# Load_Switch.net
KiCad netlist of a schematic drawn in Altium Designer
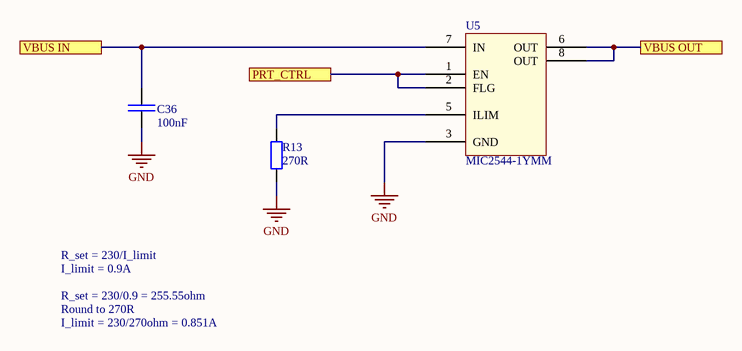
[diagram p0: Load Switch.SchDoc]

(export (version "E")
  (design (tool "Eeschema 10.0.6"))
  (components
    (comp (ref "C36")
      (value "100nF")
      (footprint "CAP_SM0603_YAGEOCC2_N")
      (description "CAP 100nF SM0603 X7R 50V YAGEO CC2")
      (fields
        (field (name "MANUFACTURER") "Yageo")
        (field (name "MANUFACTURER PART NUMBER") "CC0603KRX7R9BB104")
      )
      (libsource (lib "Yageo") (part "CC0603KRX7R9BB104"))
    )
    (comp (ref "R13")
      (value "270R")
      (footprint "RES_SM0603_YAGEORC_N")
      (description "RES 270R SM0603 YAGEO RC_L")
      (fields
        (field (name "MANUFACTURER") "Yageo")
        (field (name "MANUFACTURER PART NUMBER") "RC0603FR-07270RL")
      )
      (libsource (lib "Yageo") (part "RC0603FR-07270RL"))
    )
    (comp (ref "U5")
      (value "MIC2544-1YMM")
      (footprint "TSOP65P490X110-8N - MIC2544-1YMM")
      (description "IC PWR SWITCH N-CHAN 1:1 8MSOP")
      (libsource (lib "KBuchka-IntLib") (part "MIC2544-1YMM"))
    )
  )
  (nets
    (net (code "1") (name "/PRT_CTRL") (class "Default")
      (node (ref "U5") (pin "1") (pinfunction "EN_1") (pintype "passive"))
      (node (ref "U5") (pin "2") (pinfunction "FLG_2") (pintype "passive"))
    )
    (net (code "2") (name "/VBUS IN") (class "Default")
      (node (ref "C36") (pin "1") (pintype "passive"))
      (node (ref "U5") (pin "7") (pinfunction "IN_7") (pintype "passive"))
    )
    (net (code "3") (name "/VBUS OUT") (class "Default")
      (node (ref "U5") (pin "6") (pinfunction "OUT_6") (pintype "passive"))
      (node (ref "U5") (pin "8") (pinfunction "OUT_8") (pintype "passive"))
    )
    (net (code "4") (name "GND") (class "Default")
      (node (ref "C36") (pin "2") (pintype "passive"))
      (node (ref "R13") (pin "1") (pintype "passive"))
      (node (ref "U5") (pin "3") (pinfunction "GND_3") (pintype "passive"))
    )
    (net (code "5") (name "Net-(U5-ILIM)") (class "Default")
      (node (ref "R13") (pin "2") (pintype "passive"))
      (node (ref "U5") (pin "5") (pinfunction "ILIM_5") (pintype "passive"))
    )
  )
)
